# CPU_MISC.net
KiCad netlist of a schematic drawn in Altium Designer
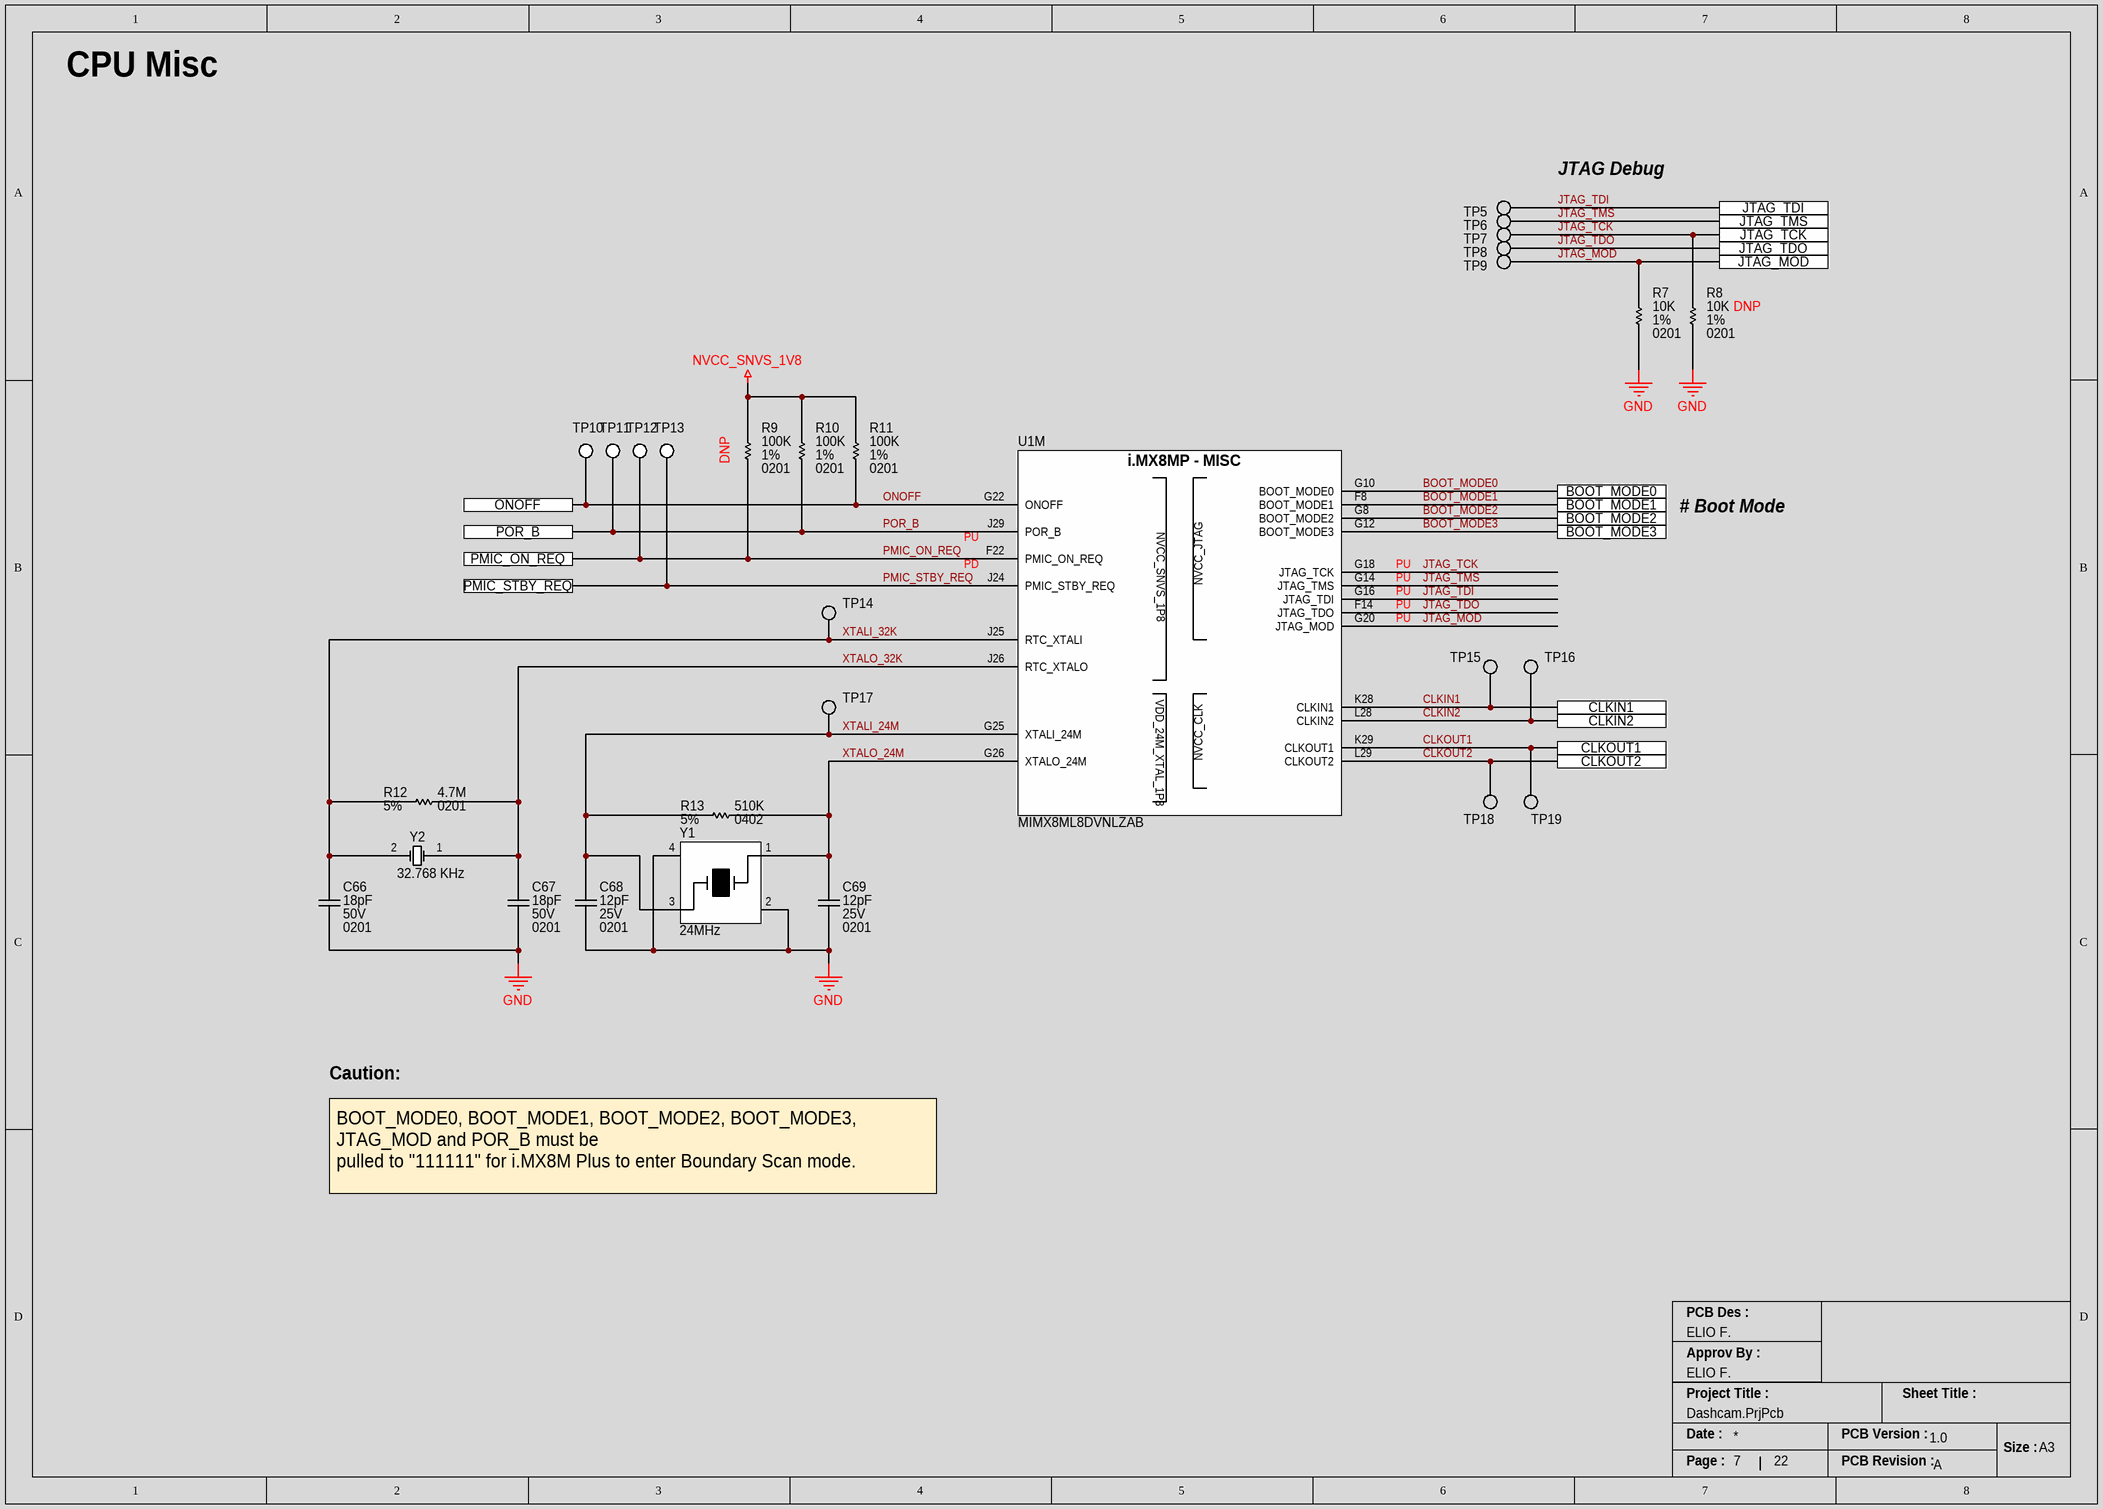
[diagram p0: CPU MISC.SchDoc]

(export (version "E")
  (design (tool "Eeschema 10.0.6"))
  (components
    (comp (ref "C66")
      (value "GRM0335C1H180JA01D")
      (footprint "CAP_0201_CAPC0603X03N")
      (description "Multilayer Ceramic Capacitor, 18 pF, 50 V, ± 5%, C0G (NP0), 0201 [0603 Metric]")
      (fields
        (field (name "MANUFACTURER") "Murata")
        (field (name "TOLERANCE") "5%")
        (field (name "CAPACITANCE") "18pF")
        (field (name "VOLTAGE RATING") "50V")
        (field (name "CASE/PACKAGE") "0201")
      )
      (libsource (lib "Electronic Devices_LIB") (part "CAP_18PF_50V_NP0_0201"))
    )
    (comp (ref "C67")
      (value "GRM0335C1H180JA01D")
      (footprint "CAP_0201_CAPC0603X03N")
      (description "Multilayer Ceramic Capacitor, 18 pF, 50 V, ± 5%, C0G (NP0), 0201 [0603 Metric]")
      (fields
        (field (name "MANUFACTURER") "Murata")
        (field (name "TOLERANCE") "5%")
        (field (name "CAPACITANCE") "18pF")
        (field (name "VOLTAGE RATING") "50V")
        (field (name "CASE/PACKAGE") "0201")
      )
      (libsource (lib "Electronic Devices_LIB") (part "CAP_18PF_50V_NP0_0201"))
    )
    (comp (ref "C68")
      (value "CGA1A2C0G1E120J030BA")
      (footprint "CAP_0201_CAPC0603X03N")
      (description "CAPACITORS CERAMIC, 12PF, 5%, 25V, C0G, 0201[0603]; Product Range: TDK - CGA Seri")
      (fields
        (field (name "MANUFACTURER") "TDK")
        (field (name "TOLERANCE") "5%")
        (field (name "VOLTAGE RATING") "25V")
        (field (name "CAPACITANCE") "12pF")
        (field (name "CASE/PACKAGE") "0201")
      )
      (libsource (lib "Electronic Devices_LIB") (part "CAP_12PF_25V_NP0_0201"))
    )
    (comp (ref "C69")
      (value "CGA1A2C0G1E120J030BA")
      (footprint "CAP_0201_CAPC0603X03N")
      (description "CAPACITORS CERAMIC, 12PF, 5%, 25V, C0G, 0201[0603]; Product Range: TDK - CGA Seri")
      (fields
        (field (name "MANUFACTURER") "TDK")
        (field (name "TOLERANCE") "5%")
        (field (name "VOLTAGE RATING") "25V")
        (field (name "CAPACITANCE") "12pF")
        (field (name "CASE/PACKAGE") "0201")
      )
      (libsource (lib "Electronic Devices_LIB") (part "CAP_12PF_25V_NP0_0201"))
    )
    (comp (ref "R7")
      (value "RC0201FR-0710KL")
      (footprint "RES_0201_RESC0603X02N")
      (description "SMD Chip Resistor, 10 kOhm, ± 1%, 50 mW, 0201 [0603 Metric], Thick Film, General Purpose")
      (fields
        (field (name "MANUFACTURER") "Yageo")
        (field (name "TOLERANCE") "1%")
        (field (name "RESISTANCE") "10K")
        (field (name "CASE CODE (IMPERIAL)") "0201")
      )
      (libsource (lib "Electronic Devices_LIB") (part "RES_10K_1/12W_1%_0201"))
    )
    (comp (ref "R8")
      (value "RC0201FR-0710KL")
      (footprint "RES_0201_RESC0603X02N")
      (description "SMD Chip Resistor, 10 kOhm, ± 1%, 50 mW, 0201 [0603 Metric], Thick Film, General Purpose")
      (fields
        (field (name "MANUFACTURER") "Yageo")
        (field (name "TOLERANCE") "1%")
        (field (name "RESISTANCE") "10K")
        (field (name "CASE CODE (IMPERIAL)") "0201")
      )
      (libsource (lib "Electronic Devices_LIB") (part "RES_10K_1/12W_1%_0201"))
    )
    (comp (ref "R9")
      (value "RC0201FR-07100KL")
      (footprint "RES_0201_RESC0603X02N")
      (description "SMD Chip Resistor, 100 kOhm, ± 1%, 50 mW, 0201 [0603 Metric], Thick Film, General Purpose")
      (fields
        (field (name "MANUFACTURER") "Yageo")
        (field (name "RESISTANCE") "100K")
        (field (name "TOLERANCE") "1%")
        (field (name "CASE/PACKAGE") "0201")
      )
      (libsource (lib "Electronic Devices_LIB") (part "RES_100K_1%_50mW_0201"))
    )
    (comp (ref "R10")
      (value "RC0201FR-07100KL")
      (footprint "RES_0201_RESC0603X02N")
      (description "SMD Chip Resistor, 100 kOhm, ± 1%, 50 mW, 0201 [0603 Metric], Thick Film, General Purpose")
      (fields
        (field (name "MANUFACTURER") "Yageo")
        (field (name "RESISTANCE") "100K")
        (field (name "TOLERANCE") "1%")
        (field (name "CASE/PACKAGE") "0201")
      )
      (libsource (lib "Electronic Devices_LIB") (part "RES_100K_1%_50mW_0201"))
    )
    (comp (ref "R11")
      (value "RC0201FR-07100KL")
      (footprint "RES_0201_RESC0603X02N")
      (description "SMD Chip Resistor, 100 kOhm, ± 1%, 50 mW, 0201 [0603 Metric], Thick Film, General Purpose")
      (fields
        (field (name "MANUFACTURER") "Yageo")
        (field (name "RESISTANCE") "100K")
        (field (name "TOLERANCE") "1%")
        (field (name "CASE/PACKAGE") "0201")
      )
      (libsource (lib "Electronic Devices_LIB") (part "RES_100K_1%_50mW_0201"))
    )
    (comp (ref "R12")
      (value "RC0201JR-074M7L")
      (footprint "RES_0201_RESC0603X02N")
      (description "SMD Chip Resistor, 4.7 MOhm, ± 5%, 50 mW, 0201 [0603 Metric], Thick Film, General Purpose")
      (fields
        (field (name "MANUFACTURER") "Yageo")
        (field (name "TOLERANCE") "5%")
        (field (name "RESISTANCE") "4.7M")
        (field (name "CASE/PACKAGE") "0201")
      )
      (libsource (lib "Electronic Devices_LIB") (part "RES_4.7M_5%_50mW_0201"))
    )
    (comp (ref "R13")
      (value "ERJ-2GEJ514X")
      (footprint "RES_0402_RESC1005X04N")
      (description "SMD Chip Resistor, 510 kOhm, ± 5%, 100 mW, 0402 [1005 Metric], Thick Film, General Purpose")
      (fields
        (field (name "MANUFACTURER") "Panasonic")
        (field (name "TOLERANCE") "5%")
        (field (name "RESISTANCE") "510K")
        (field (name "CASE/PACKAGE") "0402")
      )
      (libsource (lib "Electronic Devices_LIB") (part "RES_510K_5%_100mW_0402"))
    )
    (comp (ref "TP5")
      (value "NO COMPONENT")
      (footprint "TP_PAD_0.5MM_SMD_ROUND")
      (description "Test Point, SMD pad, round, 1.5mm, 1.6mm, 3mm diameter")
      (libsource (lib "Electronic Devices_LIB") (part "TP_PAD_SMD_SMALL"))
    )
    (comp (ref "TP6")
      (value "NO COMPONENT")
      (footprint "TP_PAD_0.5MM_SMD_ROUND")
      (description "Test Point, SMD pad, round, 1.5mm, 1.6mm, 3mm diameter")
      (libsource (lib "Electronic Devices_LIB") (part "TP_PAD_SMD_SMALL"))
    )
    (comp (ref "TP7")
      (value "NO COMPONENT")
      (footprint "TP_PAD_0.5MM_SMD_ROUND")
      (description "Test Point, SMD pad, round, 1.5mm, 1.6mm, 3mm diameter")
      (libsource (lib "Electronic Devices_LIB") (part "TP_PAD_SMD_SMALL"))
    )
    (comp (ref "TP8")
      (value "NO COMPONENT")
      (footprint "TP_PAD_0.5MM_SMD_ROUND")
      (description "Test Point, SMD pad, round, 1.5mm, 1.6mm, 3mm diameter")
      (libsource (lib "Electronic Devices_LIB") (part "TP_PAD_SMD_SMALL"))
    )
    (comp (ref "TP9")
      (value "NO COMPONENT")
      (footprint "TP_PAD_0.5MM_SMD_ROUND")
      (description "Test Point, SMD pad, round, 1.5mm, 1.6mm, 3mm diameter")
      (libsource (lib "Electronic Devices_LIB") (part "TP_PAD_SMD_SMALL"))
    )
    (comp (ref "TP10")
      (value "NO COMPONENT")
      (footprint "TP_PAD_0.8MM_SMD_ROUND")
      (description "Test Point, SMD pad, round, 1.5mm, 1.6mm, 3mm diameter")
      (libsource (lib "Electronic Devices_LIB") (part "TP_PAD_SMD_Round"))
    )
    (comp (ref "TP11")
      (value "NO COMPONENT")
      (footprint "TP_PAD_0.8MM_SMD_ROUND")
      (description "Test Point, SMD pad, round, 1.5mm, 1.6mm, 3mm diameter")
      (libsource (lib "Electronic Devices_LIB") (part "TP_PAD_SMD_Round"))
    )
    (comp (ref "TP12")
      (value "NO COMPONENT")
      (footprint "TP_PAD_0.8MM_SMD_ROUND")
      (description "Test Point, SMD pad, round, 1.5mm, 1.6mm, 3mm diameter")
      (libsource (lib "Electronic Devices_LIB") (part "TP_PAD_SMD_Round"))
    )
    (comp (ref "TP13")
      (value "NO COMPONENT")
      (footprint "TP_PAD_0.8MM_SMD_ROUND")
      (description "Test Point, SMD pad, round, 1.5mm, 1.6mm, 3mm diameter")
      (libsource (lib "Electronic Devices_LIB") (part "TP_PAD_SMD_Round"))
    )
    (comp (ref "TP14")
      (value "NO COMPONENT")
      (footprint "TP_PAD_0.5MM_SMD_ROUND")
      (description "Test Point, SMD pad, round, 1.5mm, 1.6mm, 3mm diameter")
      (libsource (lib "Electronic Devices_LIB") (part "TP_PAD_SMD_SMALL"))
    )
    (comp (ref "TP15")
      (value "NO COMPONENT")
      (footprint "TP_PAD_0.5MM_SMD_ROUND")
      (description "Test Point, SMD pad, round, 1.5mm, 1.6mm, 3mm diameter")
      (libsource (lib "Electronic Devices_LIB") (part "TP_PAD_SMD_SMALL"))
    )
    (comp (ref "TP16")
      (value "NO COMPONENT")
      (footprint "TP_PAD_0.5MM_SMD_ROUND")
      (description "Test Point, SMD pad, round, 1.5mm, 1.6mm, 3mm diameter")
      (libsource (lib "Electronic Devices_LIB") (part "TP_PAD_SMD_SMALL"))
    )
    (comp (ref "TP17")
      (value "NO COMPONENT")
      (footprint "TP_PAD_0.5MM_SMD_ROUND")
      (description "Test Point, SMD pad, round, 1.5mm, 1.6mm, 3mm diameter")
      (libsource (lib "Electronic Devices_LIB") (part "TP_PAD_SMD_SMALL"))
    )
    (comp (ref "TP18")
      (value "NO COMPONENT")
      (footprint "TP_PAD_0.5MM_SMD_ROUND")
      (description "Test Point, SMD pad, round, 1.5mm, 1.6mm, 3mm diameter")
      (libsource (lib "Electronic Devices_LIB") (part "TP_PAD_SMD_SMALL"))
    )
    (comp (ref "TP19")
      (value "NO COMPONENT")
      (footprint "TP_PAD_0.5MM_SMD_ROUND")
      (description "Test Point, SMD pad, round, 1.5mm, 1.6mm, 3mm diameter")
      (libsource (lib "Electronic Devices_LIB") (part "TP_PAD_SMD_SMALL"))
    )
    (comp (ref "U1")
      (value "MIMX8ML8DVNLZAB")
      (footprint "IC_MPU_BGA548C50P29X29_1500X1500X148")
      (description "i.MX 8M Plus, Consumer, / TRAY TRAY MULTIPLE DP BAKEABLE RoHS Compliant: Yes")
      (fields (field (name "MANUFACTURER") "NXP Semiconductors"))
      (libsource (lib "Electronic Devices_LIB") (part "IC_MPU_8M_PLUS_MIMX8ML8DVNLZAB"))
    )
    (comp (ref "Y1")
      (value "TSX-3225 24.0000MF15X-AC3")
      (footprint "CRYSTAL_24MHz_OSCCC320X250X60")
      (description "24 MHz ±10ppm Crystal 9pF 40 Ohms 4-SMD, No Lead")
      (fields (field (name "MANUFACTURER") "Epson") (field (name "FREQUENCY") "24MHz"))
      (libsource (lib "Electronic Devices_LIB") (part "CRYSTAL_EPSON_24MHz_TSX-3225 24.0000MF15X-AC3"))
    )
    (comp (ref "Y2")
      (value "ABS07-32.768KHZ-T")
      (footprint "CRYSTAL_ABS07-32.768KHZ-T")
      (description "Crystal 0.032768MHz ±20ppm (Tol) 12.5pF Flexural 70000Ohm 2-Pin CSMD T/R")
      (fields
        (field (name "MANUFACTURER") "Abracon")
        (field (name "TOLERANCE") "20ppm")
        (field (name "OPERATING FREQUENCY") "32.768 KHz")
      )
      (libsource (lib "Electronic Devices_LIB") (part "CRYSTAL_ABRACON_32.768KHz_ABS07-32.768KHZ-T"))
    )
  )
  (nets
    (net (code "1") (name "/BOOT_MODE0") (class "Default")
      (node (ref "U1") (pin "G10") (pinfunction "BOOT_MODE0_G10") (pintype "passive"))
    )
    (net (code "2") (name "/BOOT_MODE1") (class "Default")
      (node (ref "U1") (pin "F8") (pinfunction "BOOT_MODE1_F8") (pintype "passive"))
    )
    (net (code "3") (name "/BOOT_MODE2") (class "Default")
      (node (ref "U1") (pin "G8") (pinfunction "BOOT_MODE2_G8") (pintype "passive"))
    )
    (net (code "4") (name "/BOOT_MODE3") (class "Default")
      (node (ref "U1") (pin "G12") (pinfunction "BOOT_MODE3_G12") (pintype "passive"))
    )
    (net (code "5") (name "/CLKIN1") (class "Default")
      (node (ref "TP15") (pin "1") (pinfunction "1_1") (pintype "passive"))
      (node (ref "U1") (pin "K28") (pinfunction "CLKIN1_K28") (pintype "passive"))
    )
    (net (code "6") (name "/CLKIN2") (class "Default")
      (node (ref "TP16") (pin "1") (pinfunction "1_1") (pintype "passive"))
      (node (ref "U1") (pin "L28") (pinfunction "CLKIN2_L28") (pintype "passive"))
    )
    (net (code "7") (name "/CLKOUT1") (class "Default")
      (node (ref "TP19") (pin "1") (pinfunction "1_1") (pintype "passive"))
      (node (ref "U1") (pin "K29") (pinfunction "CLKOUT1_K29") (pintype "passive"))
    )
    (net (code "8") (name "/CLKOUT2") (class "Default")
      (node (ref "TP18") (pin "1") (pinfunction "1_1") (pintype "passive"))
      (node (ref "U1") (pin "L29") (pinfunction "CLKOUT2_L29") (pintype "passive"))
    )
    (net (code "9") (name "/JTAG_MOD") (class "Default")
      (node (ref "R7") (pin "2") (pinfunction "2_2") (pintype "passive"))
      (node (ref "TP9") (pin "1") (pinfunction "1_1") (pintype "passive"))
      (node (ref "U1") (pin "G20") (pinfunction "JTAG_MOD_G20") (pintype "passive"))
    )
    (net (code "10") (name "/JTAG_TCK") (class "Default")
      (node (ref "R8") (pin "2") (pinfunction "2_2") (pintype "passive"))
      (node (ref "TP7") (pin "1") (pinfunction "1_1") (pintype "passive"))
      (node (ref "U1") (pin "G18") (pinfunction "JTAG_TCK_G18") (pintype "passive"))
    )
    (net (code "11") (name "/JTAG_TDI") (class "Default")
      (node (ref "TP5") (pin "1") (pinfunction "1_1") (pintype "passive"))
      (node (ref "U1") (pin "G16") (pinfunction "JTAG_TDI_G16") (pintype "passive"))
    )
    (net (code "12") (name "/JTAG_TDO") (class "Default")
      (node (ref "TP8") (pin "1") (pinfunction "1_1") (pintype "passive"))
      (node (ref "U1") (pin "F14") (pinfunction "JTAG_TDO_F14") (pintype "passive"))
    )
    (net (code "13") (name "/JTAG_TMS") (class "Default")
      (node (ref "TP6") (pin "1") (pinfunction "1_1") (pintype "passive"))
      (node (ref "U1") (pin "G14") (pinfunction "JTAG_TMS_G14") (pintype "passive"))
    )
    (net (code "14") (name "/ONOFF") (class "Default")
      (node (ref "R11") (pin "1") (pinfunction "1_1") (pintype "passive"))
      (node (ref "TP10") (pin "1") (pinfunction "1_1") (pintype "passive"))
      (node (ref "U1") (pin "G22") (pinfunction "ONOFF_G22") (pintype "passive"))
    )
    (net (code "15") (name "/PMIC_ON_REQ") (class "Default")
      (node (ref "R9") (pin "1") (pinfunction "1_1") (pintype "passive"))
      (node (ref "TP12") (pin "1") (pinfunction "1_1") (pintype "passive"))
      (node (ref "U1") (pin "F22") (pinfunction "PMIC_ON_REQ_F22") (pintype "passive"))
    )
    (net (code "16") (name "/PMIC_STBY_REQ") (class "Default")
      (node (ref "TP13") (pin "1") (pinfunction "1_1") (pintype "passive"))
      (node (ref "U1") (pin "J24") (pinfunction "PMIC_STBY_REQ_J24") (pintype "passive"))
    )
    (net (code "17") (name "/POR_B") (class "Default")
      (node (ref "R10") (pin "1") (pinfunction "1_1") (pintype "passive"))
      (node (ref "TP11") (pin "1") (pinfunction "1_1") (pintype "passive"))
      (node (ref "U1") (pin "J29") (pinfunction "POR_B_J29") (pintype "passive"))
    )
    (net (code "18") (name "/XTALI_24M") (class "Default")
      (node (ref "C68") (pin "2") (pinfunction "2_2") (pintype "passive"))
      (node (ref "R13") (pin "1") (pinfunction "1_1") (pintype "passive"))
      (node (ref "TP17") (pin "1") (pinfunction "1_1") (pintype "passive"))
      (node (ref "U1") (pin "G25") (pinfunction "XTALI_24M_G25") (pintype "passive"))
      (node (ref "Y1") (pin "3") (pinfunction "3_3") (pintype "passive"))
    )
    (net (code "19") (name "/XTALI_32K") (class "Default")
      (node (ref "C66") (pin "2") (pinfunction "2_2") (pintype "passive"))
      (node (ref "R12") (pin "1") (pinfunction "1_1") (pintype "passive"))
      (node (ref "TP14") (pin "1") (pinfunction "1_1") (pintype "passive"))
      (node (ref "U1") (pin "J25") (pinfunction "RTC_XTALI_J25") (pintype "passive"))
      (node (ref "Y2") (pin "2") (pinfunction "OSC2_2") (pintype "passive"))
    )
    (net (code "20") (name "/XTALO_24M") (class "Default")
      (node (ref "C69") (pin "2") (pinfunction "2_2") (pintype "passive"))
      (node (ref "R13") (pin "2") (pinfunction "2_2") (pintype "passive"))
      (node (ref "U1") (pin "G26") (pinfunction "XTALO_24M_G26") (pintype "passive"))
      (node (ref "Y1") (pin "1") (pinfunction "1_1") (pintype "passive"))
    )
    (net (code "21") (name "/XTALO_32K") (class "Default")
      (node (ref "C67") (pin "2") (pinfunction "2_2") (pintype "passive"))
      (node (ref "R12") (pin "2") (pinfunction "2_2") (pintype "passive"))
      (node (ref "U1") (pin "J26") (pinfunction "RTC_XTALO_J26") (pintype "passive"))
      (node (ref "Y2") (pin "1") (pinfunction "OSC1_1") (pintype "passive"))
    )
    (net (code "22") (name "GND") (class "Default")
      (node (ref "C66") (pin "1") (pinfunction "1_1") (pintype "passive"))
      (node (ref "C67") (pin "1") (pinfunction "1_1") (pintype "passive"))
      (node (ref "C68") (pin "1") (pinfunction "1_1") (pintype "passive"))
      (node (ref "C69") (pin "1") (pinfunction "1_1") (pintype "passive"))
      (node (ref "R7") (pin "1") (pinfunction "1_1") (pintype "passive"))
      (node (ref "R8") (pin "1") (pinfunction "1_1") (pintype "passive"))
      (node (ref "Y1") (pin "2") (pinfunction "2_2") (pintype "passive"))
      (node (ref "Y1") (pin "4") (pinfunction "4_4") (pintype "passive"))
    )
    (net (code "23") (name "NVCC_SNVS_1V8") (class "Default")
      (node (ref "R10") (pin "2") (pinfunction "2_2") (pintype "passive"))
      (node (ref "R11") (pin "2") (pinfunction "2_2") (pintype "passive"))
      (node (ref "R9") (pin "2") (pinfunction "2_2") (pintype "passive"))
    )
  )
)
